# SCH_AVI-HUB_2026-06-03.net
KiCad netlist of a schematic drawn in EasyEDA
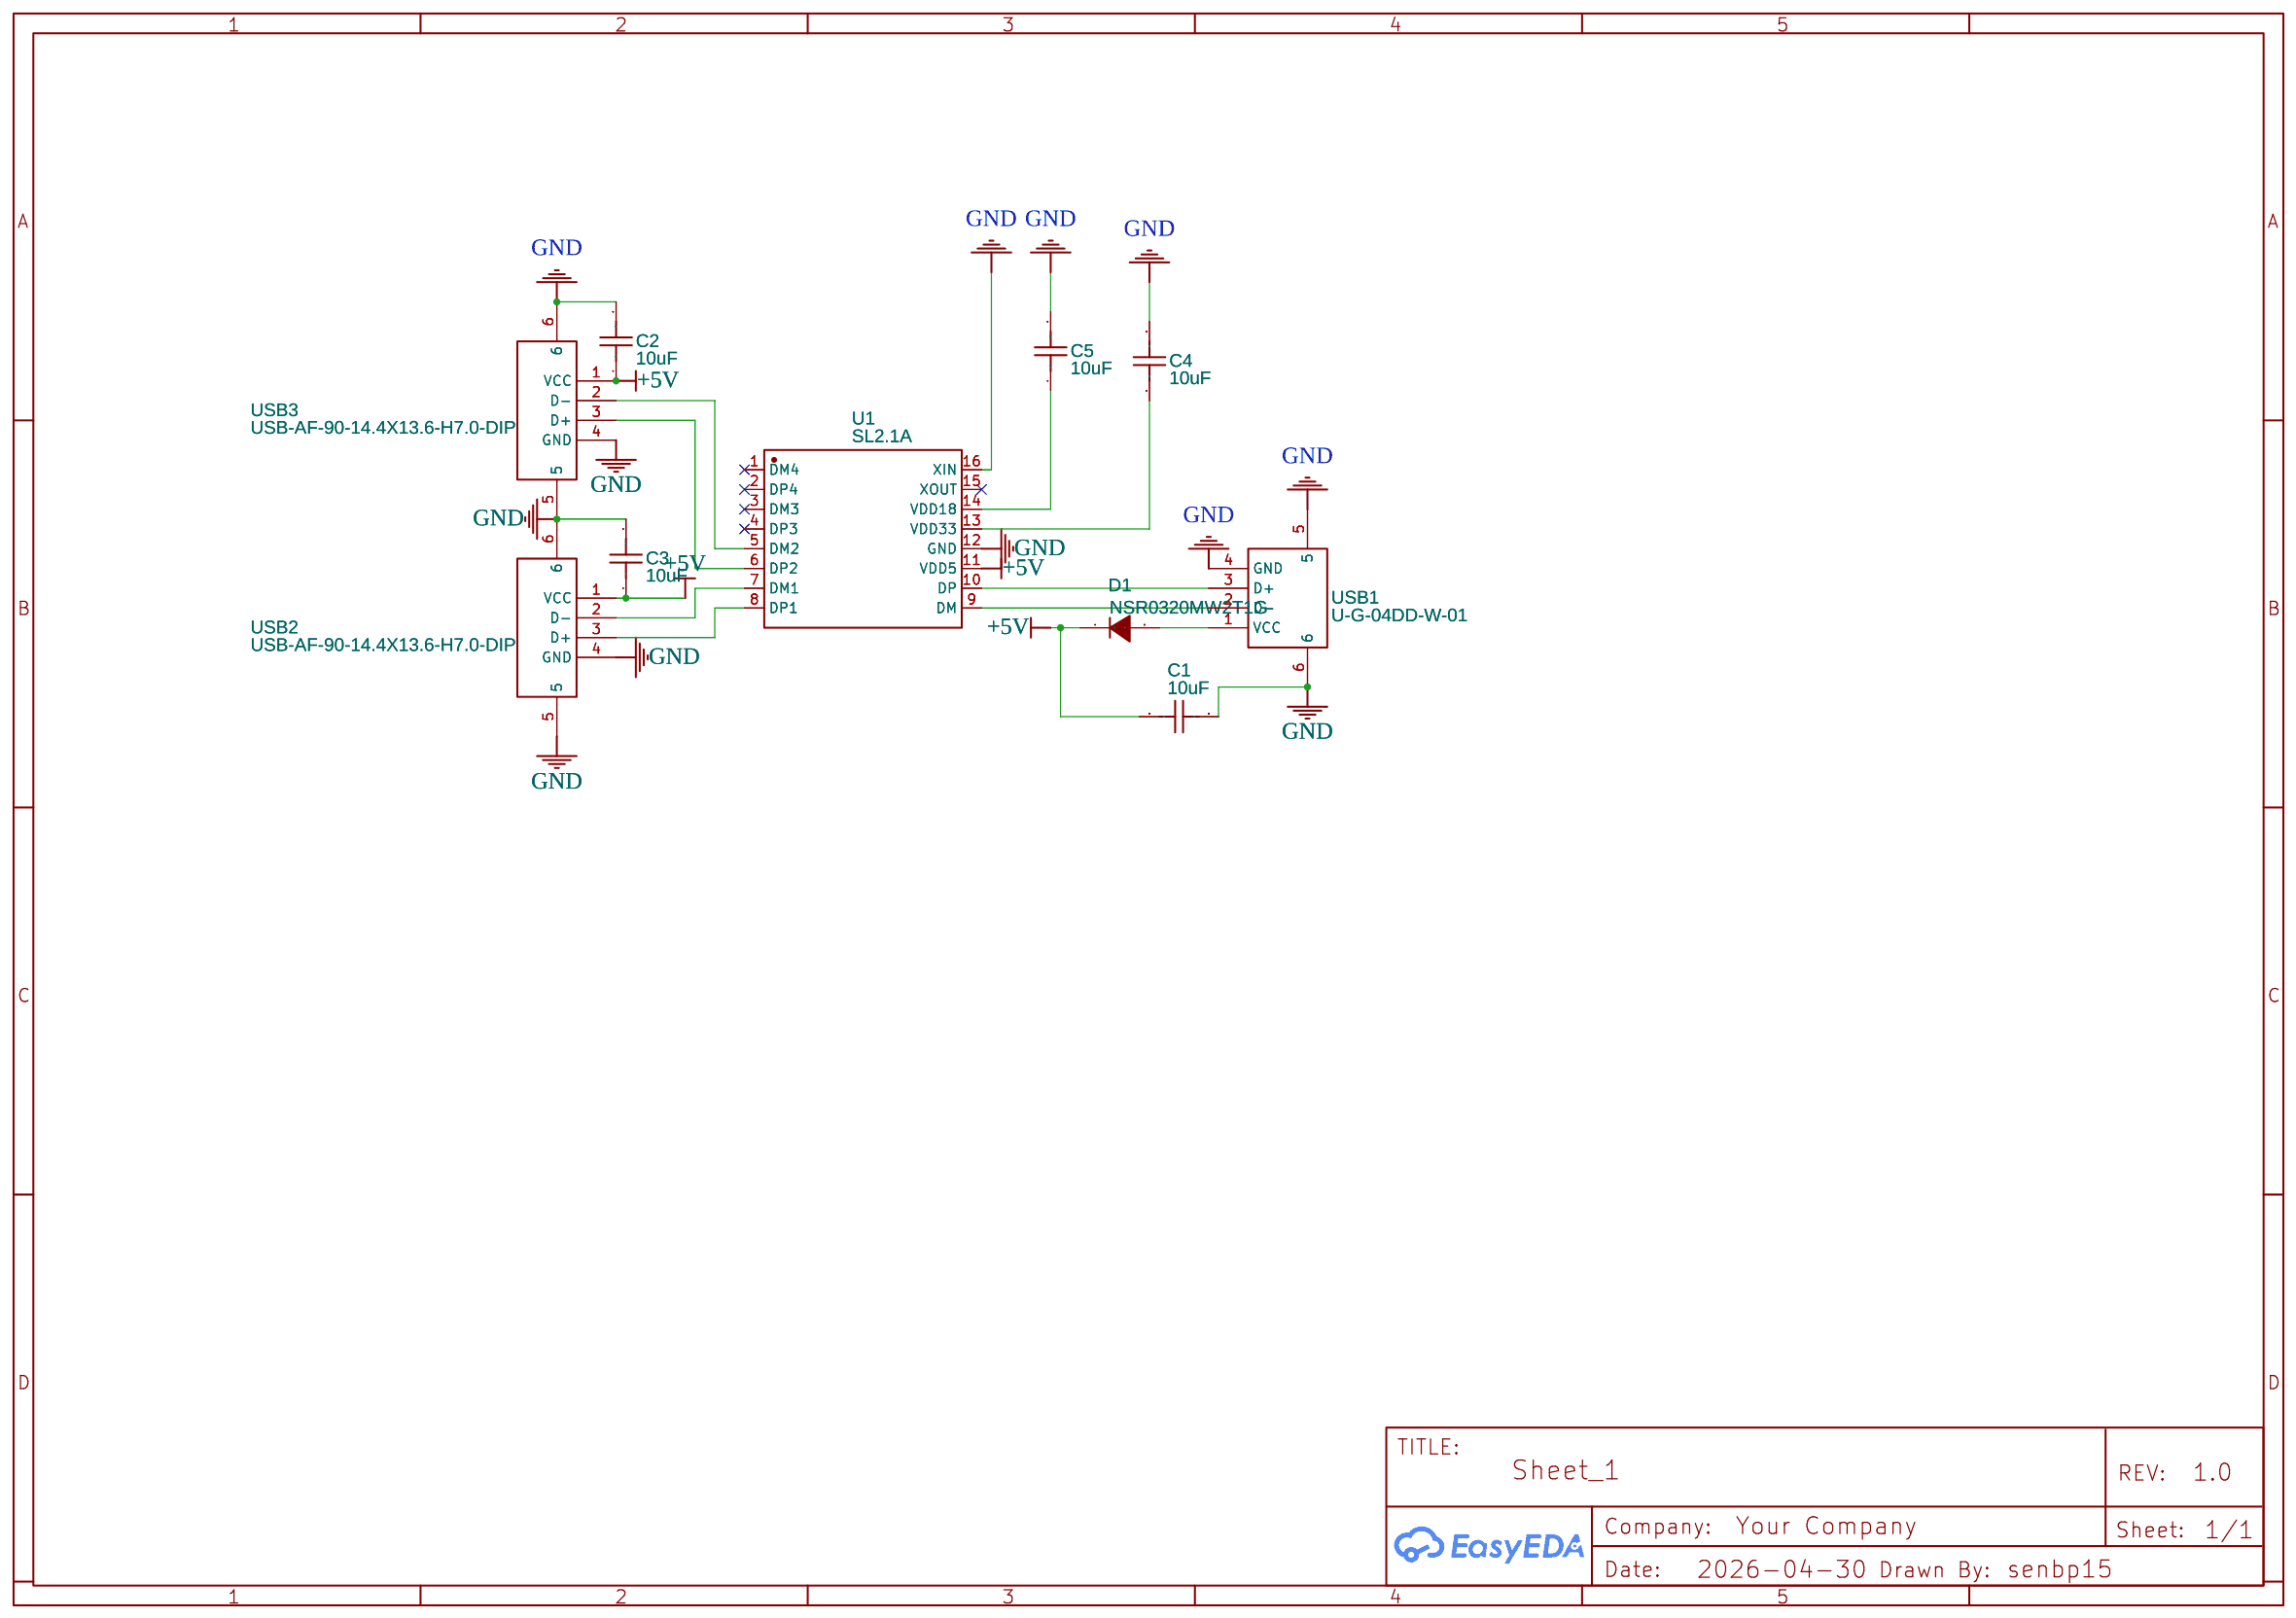
[diagram p0: schematic sheet]

(export (version "E")
  (design (tool "Eeschema 10.0.6"))
  (components
    (comp (ref "C1")
      (value "10uF")
      (fields
        (field (name "Manufacturer Part") "CL10A106KP8NNNC")
        (field (name "Manufacturer") "SAMSUNG(三星)")
      )
      (libsource (lib "") (part "CL10A106KP8NNNC"))
    )
    (comp (ref "C2")
      (value "10uF")
      (fields
        (field (name "Manufacturer Part") "CL10A106KP8NNNC")
        (field (name "Manufacturer") "SAMSUNG(三星)")
      )
      (libsource (lib "") (part "CL10A106KP8NNNC_1"))
    )
    (comp (ref "C3")
      (value "10uF")
      (fields
        (field (name "Manufacturer Part") "CL10A106KP8NNNC")
        (field (name "Manufacturer") "SAMSUNG(三星)")
      )
      (libsource (lib "") (part "CL10A106KP8NNNC_1"))
    )
    (comp (ref "C4")
      (value "10uF")
      (fields
        (field (name "Manufacturer Part") "CL10A106KP8NNNC")
        (field (name "Manufacturer") "SAMSUNG(三星)")
      )
      (libsource (lib "") (part "CL10A106KP8NNNC_1"))
    )
    (comp (ref "C5")
      (value "10uF")
      (fields
        (field (name "Manufacturer Part") "CL10A106KP8NNNC")
        (field (name "Manufacturer") "SAMSUNG(三星)")
      )
      (libsource (lib "") (part "CL10A106KP8NNNC_1"))
    )
    (comp (ref "D1")
      (value "NSR0320MW2T1G")
      (fields (field (name "Manufacturer") "onsemi(安森美)"))
      (libsource (lib "") (part "NSR0320MW2T1G"))
    )
    (comp (ref "U1")
      (value "SL2.1A")
      (fields (field (name "Manufacturer") "CoreChips(和芯润德)"))
      (libsource (lib "") (part "SL2.1A"))
    )
    (comp (ref "USB1")
      (value "U-G-04DD-W-01")
      (fields (field (name "Manufacturer Part") "U-G-O4DD-W-1") (field (name "Manufacturer") "韩国韩荣"))
      (libsource (lib "") (part "U-G-04DD-W-01"))
    )
    (comp (ref "USB2")
      (value "USB-AF-90-14.4X13.6-H7.0-DIP")
      (fields (field (name "Manufacturer Part") "903-131A1011D10100") (field (name "Manufacturer") "精拓金"))
      (libsource (lib "") (part "USB-AF-90-14.4X13.6-H7.0-DIP"))
    )
    (comp (ref "USB3")
      (value "USB-AF-90-14.4X13.6-H7.0-DIP")
      (fields (field (name "Manufacturer Part") "903-131A1011D10100") (field (name "Manufacturer") "精拓金"))
      (libsource (lib "") (part "USB-AF-90-14.4X13.6-H7.0-DIP"))
    )
  )
  (nets
    (net (code "1") (name "+5V") (class "Default")
      (node (ref "C1") (pin "1") (pinfunction "1_1") (pintype "unspecified"))
      (node (ref "C2") (pin "1") (pinfunction "1_1") (pintype "unspecified"))
      (node (ref "C3") (pin "1") (pinfunction "1_1") (pintype "unspecified"))
      (node (ref "D1") (pin "1") (pinfunction "C_1") (pintype "unspecified"))
      (node (ref "U1") (pin "11") (pinfunction "VDD5_11") (pintype "unspecified"))
      (node (ref "USB2") (pin "1") (pinfunction "VCC_1") (pintype "unspecified"))
      (node (ref "USB3") (pin "1") (pinfunction "VCC_1") (pintype "unspecified"))
    )
    (net (code "2") (name "GND") (class "Default")
      (node (ref "C1") (pin "2") (pinfunction "2_2") (pintype "unspecified"))
      (node (ref "C2") (pin "2") (pinfunction "2_2") (pintype "unspecified"))
      (node (ref "C3") (pin "2") (pinfunction "2_2") (pintype "unspecified"))
      (node (ref "C4") (pin "2") (pinfunction "2_2") (pintype "unspecified"))
      (node (ref "C5") (pin "2") (pinfunction "2_2") (pintype "unspecified"))
      (node (ref "U1") (pin "12") (pinfunction "GND_12") (pintype "unspecified"))
      (node (ref "U1") (pin "16") (pinfunction "XIN_16") (pintype "unspecified"))
      (node (ref "USB1") (pin "4") (pinfunction "GND_4") (pintype "unspecified"))
      (node (ref "USB1") (pin "5") (pinfunction "5_5") (pintype "unspecified"))
      (node (ref "USB1") (pin "6") (pinfunction "6_6") (pintype "unspecified"))
      (node (ref "USB2") (pin "4") (pinfunction "GND_4") (pintype "unspecified"))
      (node (ref "USB2") (pin "5") (pinfunction "5_5") (pintype "unspecified"))
      (node (ref "USB2") (pin "6") (pinfunction "6_6") (pintype "unspecified"))
      (node (ref "USB3") (pin "4") (pinfunction "GND_4") (pintype "unspecified"))
      (node (ref "USB3") (pin "5") (pinfunction "5_5") (pintype "unspecified"))
      (node (ref "USB3") (pin "6") (pinfunction "6_6") (pintype "unspecified"))
    )
    (net (code "3") (name "Net-(D1-A)") (class "Default")
      (node (ref "D1") (pin "2") (pinfunction "A_2") (pintype "unspecified"))
      (node (ref "USB1") (pin "1") (pinfunction "VCC_1") (pintype "unspecified"))
    )
    (net (code "4") (name "Net-(U1-DM)") (class "Default")
      (node (ref "U1") (pin "9") (pinfunction "DM_9") (pintype "unspecified"))
      (node (ref "USB1") (pin "2") (pinfunction "D-_2") (pintype "unspecified"))
    )
    (net (code "5") (name "Net-(U1-DM1)") (class "Default")
      (node (ref "U1") (pin "7") (pinfunction "DM1_7") (pintype "unspecified"))
      (node (ref "USB2") (pin "2") (pinfunction "D-_2") (pintype "unspecified"))
    )
    (net (code "6") (name "Net-(U1-DM2)") (class "Default")
      (node (ref "U1") (pin "5") (pinfunction "DM2_5") (pintype "unspecified"))
      (node (ref "USB3") (pin "2") (pinfunction "D-_2") (pintype "unspecified"))
    )
    (net (code "7") (name "Net-(U1-DP)") (class "Default")
      (node (ref "U1") (pin "10") (pinfunction "DP_10") (pintype "unspecified"))
      (node (ref "USB1") (pin "3") (pinfunction "D+_3") (pintype "unspecified"))
    )
    (net (code "8") (name "Net-(U1-DP1)") (class "Default")
      (node (ref "U1") (pin "8") (pinfunction "DP1_8") (pintype "unspecified"))
      (node (ref "USB2") (pin "3") (pinfunction "D+_3") (pintype "unspecified"))
    )
    (net (code "9") (name "Net-(U1-DP2)") (class "Default")
      (node (ref "U1") (pin "6") (pinfunction "DP2_6") (pintype "unspecified"))
      (node (ref "USB3") (pin "3") (pinfunction "D+_3") (pintype "unspecified"))
    )
    (net (code "10") (name "Net-(U1-VDD18)") (class "Default")
      (node (ref "C5") (pin "1") (pinfunction "1_1") (pintype "unspecified"))
      (node (ref "U1") (pin "14") (pinfunction "VDD18_14") (pintype "unspecified"))
    )
    (net (code "11") (name "Net-(U1-VDD33)") (class "Default")
      (node (ref "C4") (pin "1") (pinfunction "1_1") (pintype "unspecified"))
      (node (ref "U1") (pin "13") (pinfunction "VDD33_13") (pintype "unspecified"))
    )
    (net (code "12") (name "unconnected-(U1-DM3-Pad3)") (class "Default")
      (node (ref "U1") (pin "3") (pinfunction "DM3_3") (pintype "unspecified+no_connect"))
    )
    (net (code "13") (name "unconnected-(U1-DM4-Pad1)") (class "Default")
      (node (ref "U1") (pin "1") (pinfunction "DM4_1") (pintype "unspecified+no_connect"))
    )
    (net (code "14") (name "unconnected-(U1-DP3-Pad4)") (class "Default")
      (node (ref "U1") (pin "4") (pinfunction "DP3_4") (pintype "unspecified+no_connect"))
    )
    (net (code "15") (name "unconnected-(U1-DP4-Pad2)") (class "Default")
      (node (ref "U1") (pin "2") (pinfunction "DP4_2") (pintype "unspecified+no_connect"))
    )
    (net (code "16") (name "unconnected-(U1-XOUT-Pad15)") (class "Default")
      (node (ref "U1") (pin "15") (pinfunction "XOUT_15") (pintype "unspecified+no_connect"))
    )
  )
)
